# PLC1_3.net
KiCad netlist of a schematic drawn in Altium Designer
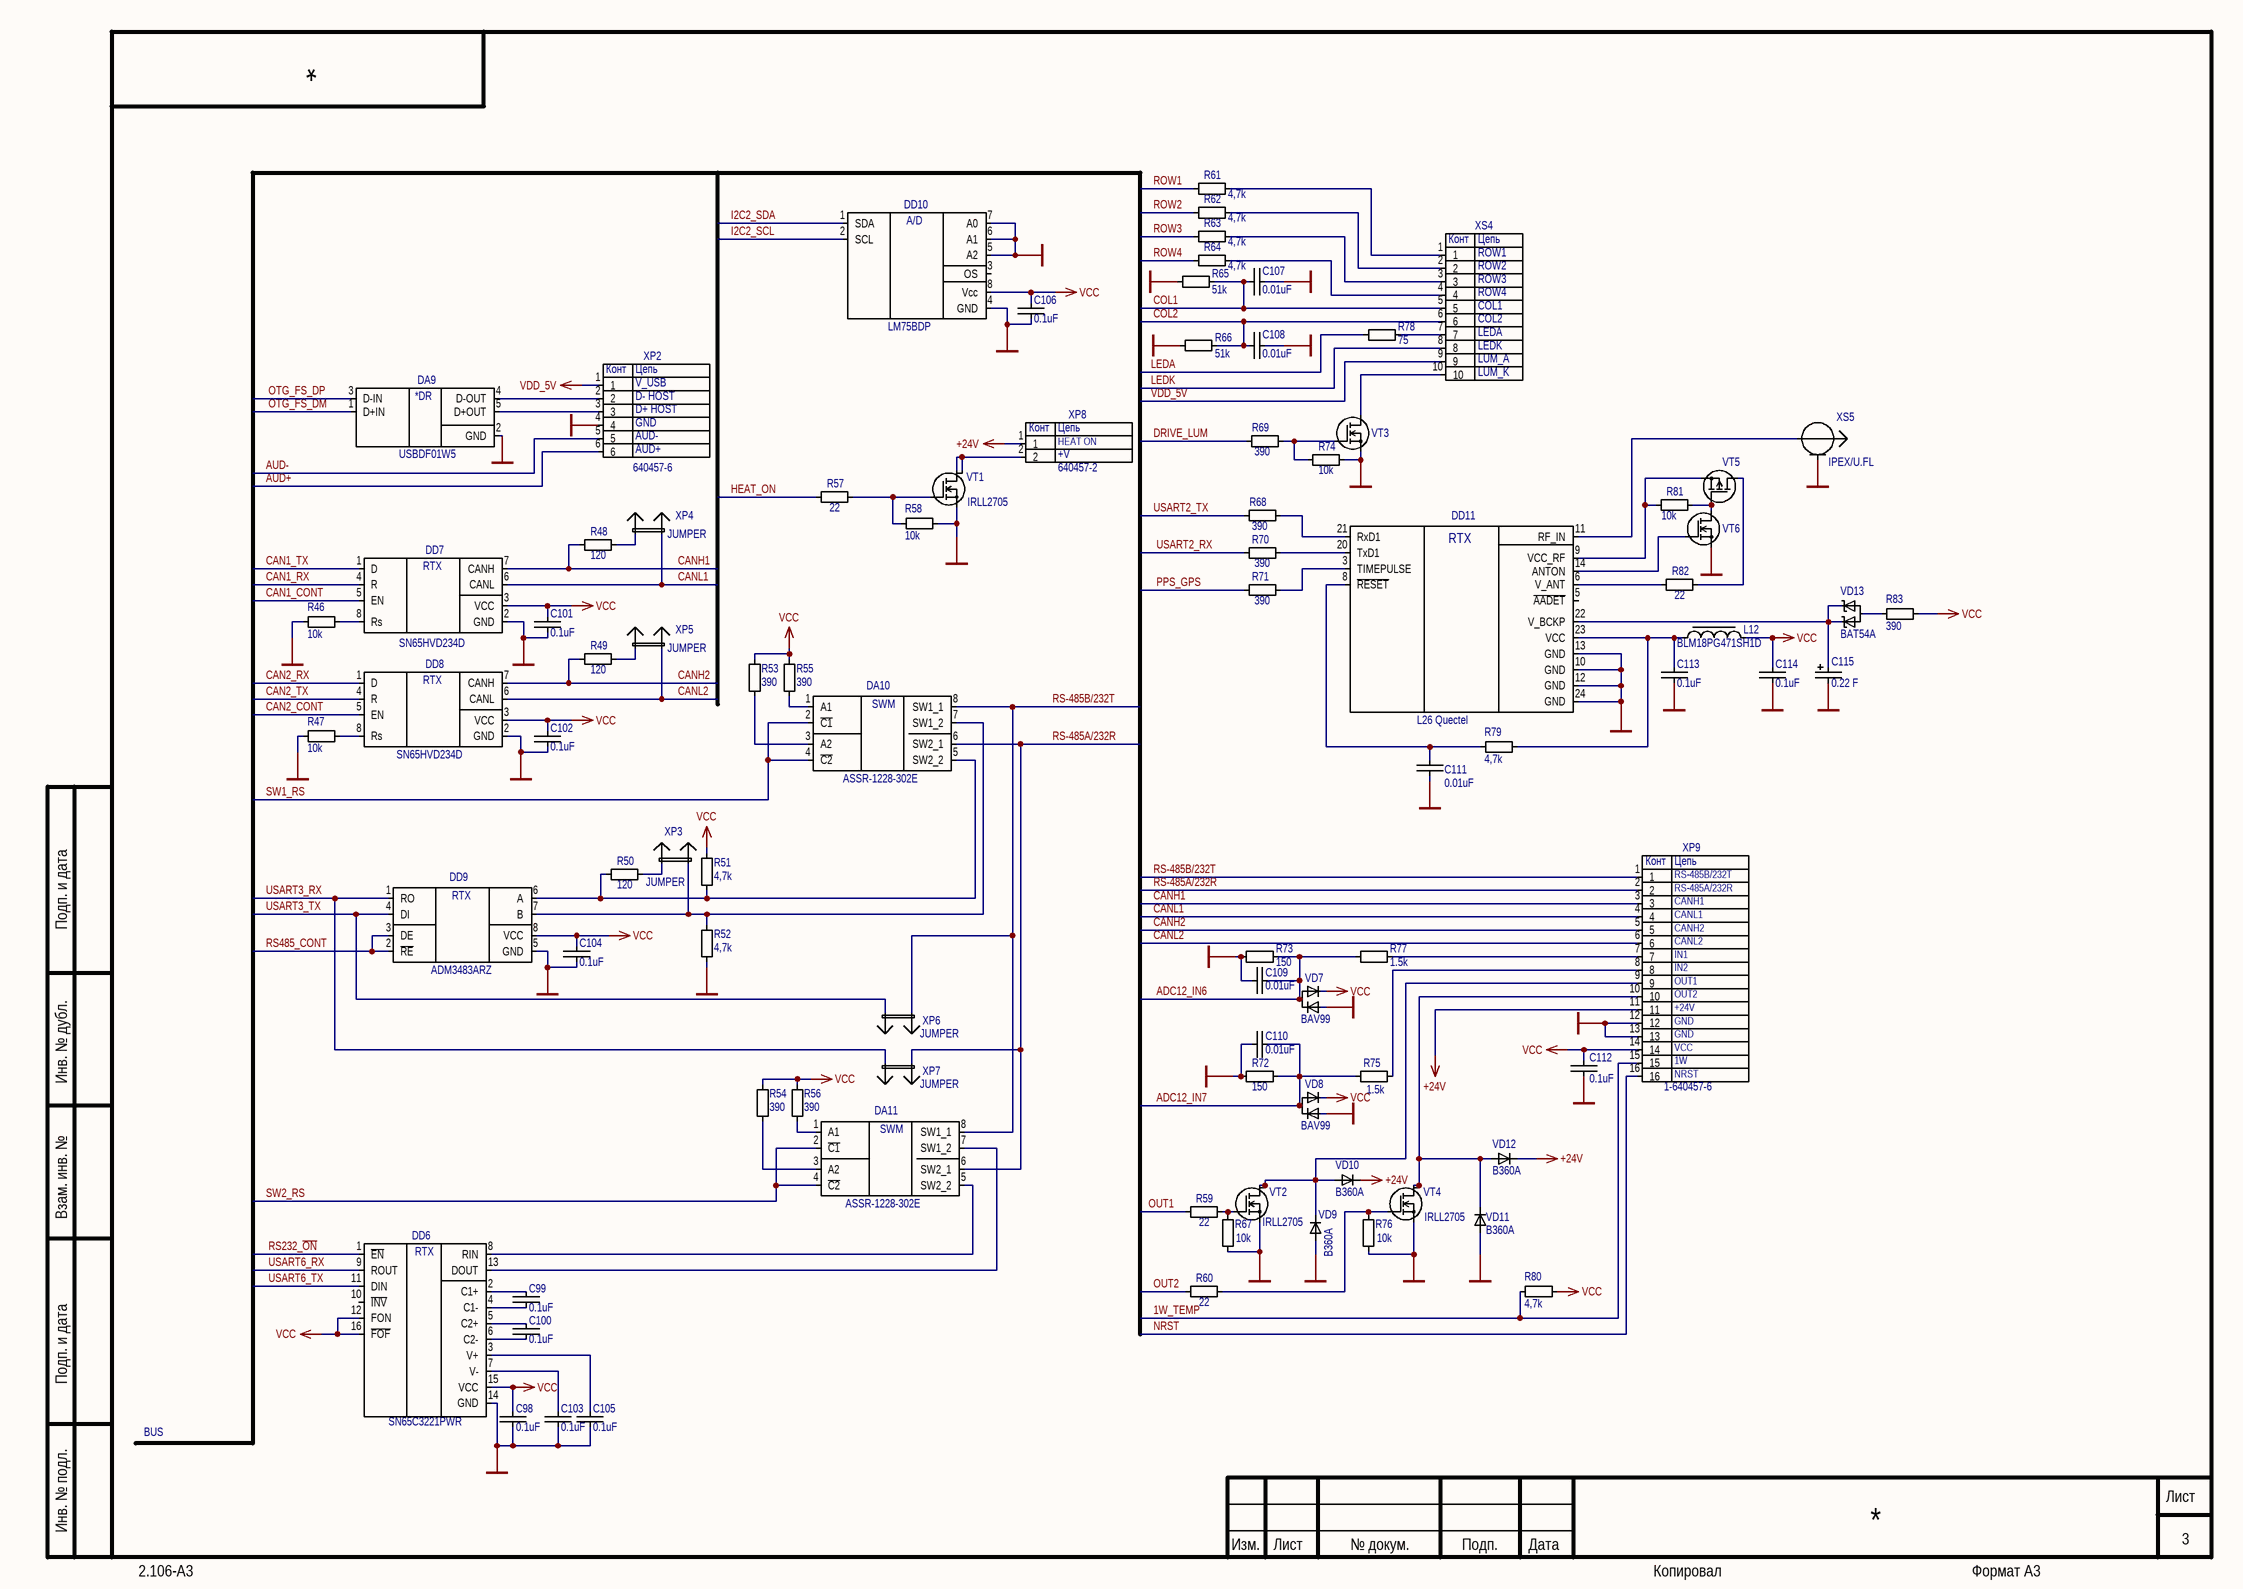
[diagram p0: PLC1_3.SchDoc]

(export (version "E")
  (design (tool "Eeschema 10.0.6"))
  (components
    (comp (ref "C98")
      (value "0.1uF")
      (footprint "CAP_0603")
      (fields (field (name "MANUFACTURER") "AVX") (field (name "PART NUMBER") "0603YC104KAT2A"))
      (libsource (lib "PLC1") (part "Cap_0603"))
    )
    (comp (ref "C99")
      (value "0.1uF")
      (footprint "CAP_0603")
      (fields (field (name "MANUFACTURER") "AVX") (field (name "PART NUMBER") "0603YC104KAT2A"))
      (libsource (lib "PLC1") (part "Cap_0603"))
    )
    (comp (ref "C100")
      (value "0.1uF")
      (footprint "CAP_0603")
      (fields (field (name "MANUFACTURER") "AVX") (field (name "PART NUMBER") "0603YC104KAT2A"))
      (libsource (lib "PLC1") (part "Cap_0603"))
    )
    (comp (ref "C101")
      (value "0.1uF")
      (footprint "CAP_0603")
      (fields (field (name "MANUFACTURER") "AVX") (field (name "PART NUMBER") "0603YC104KAT2A"))
      (libsource (lib "PLC1") (part "Cap_0603"))
    )
    (comp (ref "C102")
      (value "0.1uF")
      (footprint "CAP_0603")
      (fields (field (name "MANUFACTURER") "AVX") (field (name "PART NUMBER") "0603YC104KAT2A"))
      (libsource (lib "PLC1") (part "Cap_0603"))
    )
    (comp (ref "C103")
      (value "0.1uF")
      (footprint "CAP_0603")
      (fields (field (name "MANUFACTURER") "AVX") (field (name "PART NUMBER") "0603YC104KAT2A"))
      (libsource (lib "PLC1") (part "Cap_0603"))
    )
    (comp (ref "C104")
      (value "0.1uF")
      (footprint "CAP_0603")
      (fields (field (name "MANUFACTURER") "AVX") (field (name "PART NUMBER") "0603YC104KAT2A"))
      (libsource (lib "PLC1") (part "Cap_0603"))
    )
    (comp (ref "C105")
      (value "0.1uF")
      (footprint "CAP_0603")
      (fields (field (name "MANUFACTURER") "AVX") (field (name "PART NUMBER") "0603YC104KAT2A"))
      (libsource (lib "PLC1") (part "Cap_0603"))
    )
    (comp (ref "C106")
      (value "0.1uF")
      (footprint "CAP_0603")
      (fields (field (name "MANUFACTURER") "AVX") (field (name "PART NUMBER") "0603YC104KAT2A"))
      (libsource (lib "PLC1") (part "Cap_0603"))
    )
    (comp (ref "C107")
      (value "0.01uF")
      (footprint "CAP_0603")
      (fields (field (name "MANUFACTURER") "AVX") (field (name "PART NUMBER") "0603YC103KAT2A"))
      (libsource (lib "PLC1") (part "Cap_0603"))
    )
    (comp (ref "C108")
      (value "0.01uF")
      (footprint "CAP_0603")
      (fields (field (name "MANUFACTURER") "AVX") (field (name "PART NUMBER") "0603YC103KAT2A"))
      (libsource (lib "PLC1") (part "Cap_0603"))
    )
    (comp (ref "C109")
      (value "0.01uF")
      (footprint "CAP_0603")
      (fields (field (name "MANUFACTURER") "AVX") (field (name "PART NUMBER") "0603YC103KAT2A"))
      (libsource (lib "PLC1") (part "Cap_0603"))
    )
    (comp (ref "C110")
      (value "0.01uF")
      (footprint "CAP_0603")
      (fields (field (name "MANUFACTURER") "AVX") (field (name "PART NUMBER") "0603YC103KAT2A"))
      (libsource (lib "PLC1") (part "Cap_0603"))
    )
    (comp (ref "C111")
      (value "0.01uF")
      (footprint "CAP_0603")
      (fields (field (name "MANUFACTURER") "AVX") (field (name "PART NUMBER") "0603YC103KAT2A"))
      (libsource (lib "PLC1") (part "Cap_0603"))
    )
    (comp (ref "C112")
      (value "0.1uF")
      (footprint "CAP_0603")
      (fields (field (name "MANUFACTURER") "AVX") (field (name "PART NUMBER") "0603YC104KAT2A"))
      (libsource (lib "PLC1") (part "Cap_0603"))
    )
    (comp (ref "C113")
      (value "0.1uF")
      (footprint "CAP_0603")
      (fields (field (name "MANUFACTURER") "AVX") (field (name "PART NUMBER") "0603YC104KAT2A"))
      (libsource (lib "PLC1") (part "Cap_0603"))
    )
    (comp (ref "C114")
      (value "0.1uF")
      (footprint "CAP_0603")
      (fields (field (name "MANUFACTURER") "AVX") (field (name "PART NUMBER") "0603YC104KAT2A"))
      (libsource (lib "PLC1") (part "Cap_0603"))
    )
    (comp (ref "C115")
      (value "0.22 F")
      (footprint "KR-5R5C104-R")
      (description "supercapacitor 0.22 uF")
      (fields (field (name "MANUFACTURER") "Panasonic") (field (name "PART NUMBER") "KR-5R5C224-R"))
      (libsource (lib "PLC1") (part "KR-5R5C104-R"))
    )
    (comp (ref "DA9")
      (value "USBDF01W5")
      (footprint "SOT323-5L")
      (description "Unidirectional 2 lines Filter + ESD")
      (fields (field (name "MANUFACTURER") "ST") (field (name "PART NUMBER") "USBDF01W5"))
      (libsource (lib "PLC1") (part "USBDF01W6"))
    )
    (comp (ref "DA10")
      (value "ASSR-1228-302E")
      (footprint "DIP8_GULL")
      (description "RS-485 PHY")
      (fields (field (name "MANUFACTURER") "AVAGO") (field (name "PART NUMBER") "ASSR-1228-302E"))
      (libsource (lib "PLC1") (part "ASSR-1228-302E"))
    )
    (comp (ref "DA11")
      (value "ASSR-1228-302E")
      (footprint "DIP8_GULL")
      (description "RS-485 PHY")
      (fields (field (name "MANUFACTURER") "AVAGO") (field (name "PART NUMBER") "ASSR-1228-302E"))
      (libsource (lib "PLC1") (part "ASSR-1228-302E"))
    )
    (comp (ref "DD6")
      (value "SN65C3221PWR")
      (footprint "TSSO5x6-G16")
      (description "RS-232 PHY CAN PHY")
      (fields (field (name "MANUFACTURER") "TI") (field (name "PART NUMBER") "SN65C3221PWR"))
      (libsource (lib "PLC1") (part "SN65C3221PWR"))
    )
    (comp (ref "DD7")
      (value "SN65HVD234D")
      (footprint "SOIC8")
      (description "SN65HVD234D CAN PHY")
      (fields (field (name "MANUFACTURER") "TI") (field (name "PART NUMBER") "SN65HVD234D"))
      (libsource (lib "PLC1") (part "SN65HVD234D"))
    )
    (comp (ref "DD8")
      (value "SN65HVD234D")
      (footprint "SOIC8")
      (description "SN65HVD234D CAN PHY")
      (fields (field (name "MANUFACTURER") "TI") (field (name "PART NUMBER") "SN65HVD234D"))
      (libsource (lib "PLC1") (part "SN65HVD234D"))
    )
    (comp (ref "DD9")
      (value "ADM3483")
      (footprint "SOIC8")
      (description "RS-485 PHY")
      (fields (field (name "MANUFACTURER") "Analog Devices") (field (name "PART NUMBER") "ADM3483ARZ"))
      (libsource (lib "PLC1") (part "ADM3483"))
    )
    (comp (ref "DD10")
      (value "LM75BDP")
      (footprint "TSSO3x5-G8/X.4")
      (description "LM75BDP TEMPERATURE SENSOR")
      (fields (field (name "MANUFACTURER") "NXP") (field (name "PART NUMBER") "LM75BDP"))
      (libsource (lib "PLC1") (part "LM75BDP"))
    )
    (comp (ref "DD11")
      (value "L26 Quectel")
      (footprint "VK1612U")
      (description "GPS receiver")
      (fields (field (name "MANUFACTURER") "Quectel") (field (name "PART NUMBER") "L26 Quectel"))
      (libsource (lib "PLC1") (part "L26 Quectel"))
    )
    (comp (ref "L12")
      (value "BLM18PG471SH1D")
      (footprint "R_IND_0603")
      (fields (field (name "MANUFACTURER") "Murata"))
      (libsource (lib "PLC1") (part "FCM1608KF-601T03"))
    )
    (comp (ref "R46")
      (value "10k")
      (footprint "RES_0603")
      (description "0603, 10k")
      (fields (field (name "MANUFACTURER") "Vishay") (field (name "PART NUMBER") "CRCW060310K0JNE"))
      (libsource (lib "PLC1") (part "Res_0603"))
    )
    (comp (ref "R47")
      (value "10k")
      (footprint "RES_0603")
      (description "0603, 10k")
      (fields (field (name "MANUFACTURER") "Vishay") (field (name "PART NUMBER") "CRCW060310K0JNE"))
      (libsource (lib "PLC1") (part "Res_0603"))
    )
    (comp (ref "R48")
      (value "120")
      (footprint "Res_2010")
      (description "2010")
      (fields
        (field (name "MANUFACTURER") "NIC Components Corp.")
        (field (name "PART NUMBER") "NRC50J121TRF")
      )
      (libsource (lib "PLC1") (part "Res_2010"))
    )
    (comp (ref "R49")
      (value "120")
      (footprint "Res_2010")
      (description "2010")
      (fields
        (field (name "MANUFACTURER") "NIC Components Corp.")
        (field (name "PART NUMBER") "NRC50J121TRF")
      )
      (libsource (lib "PLC1") (part "Res_2010"))
    )
    (comp (ref "R50")
      (value "120")
      (footprint "Res_2010")
      (description "2010")
      (fields
        (field (name "MANUFACTURER") "NIC Components Corp.")
        (field (name "PART NUMBER") "NRC50J121TRF")
      )
      (libsource (lib "PLC1") (part "Res_2010"))
    )
    (comp (ref "R51")
      (value "4,7k")
      (footprint "RES_0603")
      (description "0603, 100")
      (fields (field (name "MANUFACTURER") "Vishay") (field (name "PART NUMBER") "CRCW0603-472JRT1"))
      (libsource (lib "PLC1") (part "Res_0603"))
    )
    (comp (ref "R52")
      (value "4,7k")
      (footprint "RES_0603")
      (description "0603, 100")
      (fields (field (name "MANUFACTURER") "Vishay") (field (name "PART NUMBER") "CRCW0603-472JRT1"))
      (libsource (lib "PLC1") (part "Res_0603"))
    )
    (comp (ref "R53")
      (value "390")
      (footprint "RES_0603")
      (description "0603, 390")
      (fields (field (name "MANUFACTURER") "YAGEO") (field (name "PART NUMBER") "RC0603FR-07390RL"))
      (libsource (lib "PLC1") (part "Res_0603"))
    )
    (comp (ref "R54")
      (value "390")
      (footprint "RES_0603")
      (description "0603, 390")
      (fields (field (name "MANUFACTURER") "YAGEO") (field (name "PART NUMBER") "RC0603FR-07390RL"))
      (libsource (lib "PLC1") (part "Res_0603"))
    )
    (comp (ref "R55")
      (value "390")
      (footprint "RES_0603")
      (description "0603, 390")
      (fields (field (name "MANUFACTURER") "YAGEO") (field (name "PART NUMBER") "RC0603FR-07390RL"))
      (libsource (lib "PLC1") (part "Res_0603"))
    )
    (comp (ref "R56")
      (value "390")
      (footprint "RES_0603")
      (description "0603, 390")
      (fields (field (name "MANUFACTURER") "YAGEO") (field (name "PART NUMBER") "RC0603FR-07390RL"))
      (libsource (lib "PLC1") (part "Res_0603"))
    )
    (comp (ref "R57")
      (value "22")
      (footprint "RES_0603")
      (description "0603, 22")
      (fields (field (name "MANUFACTURER") "Vishay") (field (name "PART NUMBER") "CRCW020122R0JNED"))
      (libsource (lib "PLC1") (part "Res_0603"))
    )
    (comp (ref "R58")
      (value "10k")
      (footprint "RES_0603")
      (description "0603, 10k")
      (fields (field (name "MANUFACTURER") "Vishay") (field (name "PART NUMBER") "CRCW060310K0JNE"))
      (libsource (lib "PLC1") (part "Res_0603"))
    )
    (comp (ref "R59")
      (value "22")
      (footprint "RES_0603")
      (description "0603, 22")
      (fields (field (name "MANUFACTURER") "Vishay") (field (name "PART NUMBER") "CRCW020122R0JNED"))
      (libsource (lib "PLC1") (part "Res_0603"))
    )
    (comp (ref "R60")
      (value "22")
      (footprint "RES_0603")
      (description "0603, 22")
      (fields (field (name "MANUFACTURER") "Vishay") (field (name "PART NUMBER") "CRCW020122R0JNED"))
      (libsource (lib "PLC1") (part "Res_0603"))
    )
    (comp (ref "R61")
      (value "4,7k")
      (footprint "Res_0603")
      (description "0603, 100")
      (fields (field (name "MANUFACTURER") "Vishay") (field (name "PART NUMBER") "CRCW0603-472JRT1"))
      (libsource (lib "PLC1") (part "Res_0603"))
    )
    (comp (ref "R62")
      (value "4,7k")
      (footprint "Res_0603")
      (description "0603, 100")
      (fields (field (name "MANUFACTURER") "Vishay") (field (name "PART NUMBER") "CRCW0603-472JRT1"))
      (libsource (lib "PLC1") (part "Res_0603"))
    )
    (comp (ref "R63")
      (value "4,7k")
      (footprint "Res_0603")
      (description "0603, 100")
      (fields (field (name "MANUFACTURER") "Vishay") (field (name "PART NUMBER") "CRCW0603-472JRT1"))
      (libsource (lib "PLC1") (part "Res_0603"))
    )
    (comp (ref "R64")
      (value "4,7k")
      (footprint "Res_0603")
      (description "0603, 100")
      (fields (field (name "MANUFACTURER") "Vishay") (field (name "PART NUMBER") "CRCW0603-472JRT1"))
      (libsource (lib "PLC1") (part "Res_0603"))
    )
    (comp (ref "R65")
      (value "51k")
      (footprint "RES_0603")
      (description "0603, 51k")
      (fields (field (name "MANUFACTURER") "Vishay") (field (name "PART NUMBER") "CRCW0603-513JRT1"))
      (libsource (lib "PLC1") (part "Res_0603"))
    )
    (comp (ref "R66")
      (value "51k")
      (footprint "RES_0603")
      (description "0603, 51k")
      (fields (field (name "MANUFACTURER") "Vishay") (field (name "PART NUMBER") "CRCW0603-513JRT1"))
      (libsource (lib "PLC1") (part "Res_0603"))
    )
    (comp (ref "R67")
      (value "10k")
      (footprint "RES_0603")
      (description "0603, 10k")
      (fields (field (name "MANUFACTURER") "Vishay") (field (name "PART NUMBER") "CRCW060310K0JNE"))
      (libsource (lib "PLC1") (part "Res_0603"))
    )
    (comp (ref "R68")
      (value "390")
      (footprint "RES_0603")
      (description "0603, 390")
      (fields (field (name "MANUFACTURER") "YAGEO") (field (name "PART NUMBER") "RC0603FR-07390RL"))
      (libsource (lib "PLC1") (part "Res_0603"))
    )
    (comp (ref "R69")
      (value "390")
      (footprint "RES_0603")
      (description "0603, 390")
      (fields (field (name "MANUFACTURER") "YAGEO") (field (name "PART NUMBER") "RC0603FR-07390RL"))
      (libsource (lib "PLC1") (part "Res_0603"))
    )
    (comp (ref "R70")
      (value "390")
      (footprint "RES_0603")
      (description "0603, 390")
      (fields (field (name "MANUFACTURER") "YAGEO") (field (name "PART NUMBER") "RC0603FR-07390RL"))
      (libsource (lib "PLC1") (part "Res_0603"))
    )
    (comp (ref "R71")
      (value "390")
      (footprint "RES_0603")
      (description "0603, 390")
      (fields (field (name "MANUFACTURER") "YAGEO") (field (name "PART NUMBER") "RC0603FR-07390RL"))
      (libsource (lib "PLC1") (part "Res_0603"))
    )
    (comp (ref "R72")
      (value "150")
      (footprint "Res_1206")
      (fields
        (field (name "MANUFACTURER") "Vishay")
        (field (name "PART NUMBER") "CRCW1206150RFKEA")
        (field (name "Comment") "Res_1206")
      )
      (libsource (lib "PLC1") (part "Res_1206"))
    )
    (comp (ref "R73")
      (value "150")
      (footprint "Res_1206")
      (fields
        (field (name "MANUFACTURER") "Vishay")
        (field (name "PART NUMBER") "CRCW1206150RFKEA")
        (field (name "Comment") "Res_1206")
      )
      (libsource (lib "PLC1") (part "Res_1206"))
    )
    (comp (ref "R74")
      (value "10k")
      (footprint "RES_0603")
      (description "0603, 10k")
      (fields (field (name "MANUFACTURER") "Vishay") (field (name "PART NUMBER") "CRCW060310K0JNE"))
      (libsource (lib "") (part "Res_0603_1"))
    )
    (comp (ref "R75")
      (value "1.5k")
      (footprint "Res_1206")
      (fields
        (field (name "MANUFACTURER") "Vishay")
        (field (name "PART NUMBER") "CRCW12061K50FKEA")
        (field (name "Comment") "Res_1206")
      )
      (libsource (lib "PLC1") (part "Res_1206"))
    )
    (comp (ref "R76")
      (value "10k")
      (footprint "RES_0603")
      (description "0603, 10k")
      (fields (field (name "MANUFACTURER") "Vishay") (field (name "PART NUMBER") "CRCW060310K0JNE"))
      (libsource (lib "PLC1") (part "Res_0603"))
    )
    (comp (ref "R77")
      (value "1.5k")
      (footprint "Res_1206")
      (fields
        (field (name "MANUFACTURER") "Vishay")
        (field (name "PART NUMBER") "CRCW12061K50FKEA")
        (field (name "Comment") "Res_1206")
      )
      (libsource (lib "PLC1") (part "Res_1206"))
    )
    (comp (ref "R78")
      (value "75")
      (footprint "RES_0603")
      (description "0603")
      (fields (field (name "MANUFACTURER") "YAGEO") (field (name "PART NUMBER") "RC0603JR-0775RL"))
      (libsource (lib "PLC1") (part "Res_0603"))
    )
    (comp (ref "R79")
      (value "4,7k")
      (footprint "Res_0603")
      (description "0603, 100")
      (fields (field (name "MANUFACTURER") "Vishay") (field (name "PART NUMBER") "CRCW0603-472JRT1"))
      (libsource (lib "PLC1") (part "Res_0603"))
    )
    (comp (ref "R80")
      (value "4,7k")
      (footprint "Res_0603")
      (description "0603, 100")
      (fields (field (name "MANUFACTURER") "Vishay") (field (name "PART NUMBER") "CRCW0603-472JRT1"))
      (libsource (lib "PLC1") (part "Res_0603"))
    )
    (comp (ref "R81")
      (value "10k")
      (footprint "RES_0603")
      (description "0603, 10k")
      (fields (field (name "MANUFACTURER") "Vishay") (field (name "PART NUMBER") "CRCW060310K0JNE"))
      (libsource (lib "PLC1") (part "Res_0603"))
    )
    (comp (ref "R82")
      (value "22")
      (footprint "RES_0603")
      (description "0603, 22")
      (fields (field (name "MANUFACTURER") "Vishay") (field (name "PART NUMBER") "CRCW020122R0JNED"))
      (libsource (lib "PLC1") (part "Res_0603"))
    )
    (comp (ref "R83")
      (value "390")
      (footprint "RES_0603")
      (description "0603, 390")
      (fields (field (name "MANUFACTURER") "YAGEO") (field (name "PART NUMBER") "RC0603FR-07390RL"))
      (libsource (lib "PLC1") (part "Res_0603"))
    )
    (comp (ref "VD7")
      (value "BAV99")
      (footprint "SOT-23")
      (fields (field (name "MANUFACTURER") "Fairchild"))
      (libsource (lib "PLC1") (part "BAV99"))
    )
    (comp (ref "VD8")
      (value "BAV99")
      (footprint "SOT-23")
      (fields (field (name "MANUFACTURER") "Fairchild"))
      (libsource (lib "PLC1") (part "BAV99"))
    )
    (comp (ref "VD9")
      (value "B360A")
      (footprint "DO-214AC")
      (fields (field (name "PART NUMBER") "B360A") (field (name "MANUFACTURER") "VISHAY"))
      (libsource (lib "PLC1") (part "S1A"))
    )
    (comp (ref "VD10")
      (value "B360A")
      (footprint "DO-214AC")
      (fields (field (name "PART NUMBER") "B360A") (field (name "MANUFACTURER") "VISHAY"))
      (libsource (lib "") (part "S1A_1"))
    )
    (comp (ref "VD11")
      (value "B360A")
      (footprint "DO-214AC")
      (fields (field (name "PART NUMBER") "B360A") (field (name "MANUFACTURER") "VISHAY"))
      (libsource (lib "PLC1") (part "S1A"))
    )
    (comp (ref "VD12")
      (value "B360A")
      (footprint "DO-214AC")
      (fields (field (name "PART NUMBER") "B360A") (field (name "MANUFACTURER") "VISHAY"))
      (libsource (lib "PLC1") (part "S1A"))
    )
    (comp (ref "VD13") (value "BAT54A") (footprint "SOT-23") (libsource (lib "PLC1") (part "BAT54A")))
    (comp (ref "VT1")
      (value "N-CHAN_SOT-223")
      (footprint "SOT-223")
      (fields (field (name "PART NUMBER") "IRLL2705"))
      (libsource (lib "PLC1") (part "N-CHAN_SOT-223"))
    )
    (comp (ref "VT2")
      (value "N-CHAN_SOT-223")
      (footprint "SOT-223")
      (fields (field (name "PART NUMBER") "IRLL2705"))
      (libsource (lib "PLC1") (part "N-CHAN_SOT-223"))
    )
    (comp (ref "VT3")
      (value "N-CHAN_SOT-23")
      (footprint "SOT-23")
      (fields (field (name "MANUFACTURER") "IR") (field (name "PART NUMBER") "IRLML2502"))
      (libsource (lib "") (part "N-CHAN_SOT-23_1"))
    )
    (comp (ref "VT4")
      (value "N-CHAN_SOT-223")
      (footprint "SOT-223")
      (fields (field (name "PART NUMBER") "IRLL2705"))
      (libsource (lib "PLC1") (part "N-CHAN_SOT-223"))
    )
    (comp (ref "VT5")
      (value "IRLML6402")
      (footprint "SOT-23")
      (libsource (lib "PLC1") (part "P-CHAN_SOT-23"))
    )
    (comp (ref "VT6")
      (value "N-CHAN_SOT-23")
      (footprint "SOT-23")
      (fields (field (name "MANUFACTURER") "IR") (field (name "PART NUMBER") "IRLML2502"))
      (libsource (lib "PLC1") (part "N-CHAN_SOT-23"))
    )
    (comp (ref "XP2")
      (value "640457-6")
      (footprint "640457-6")
      (fields (field (name "MANUFACTURER") "TE"))
      (libsource (lib "PLC1") (part "640457-6"))
    )
    (comp (ref "XP3")
      (value "JUMPER")
      (footprint "PLS2-R")
      (description "JUMPER 2.54")
      (fields (field (name "MANUFACTURER") "TE") (field (name "PART NUMBER") "PLS-2R"))
      (libsource (lib "PLC1") (part "PLS-2 R"))
    )
    (comp (ref "XP4")
      (value "JUMPER")
      (footprint "PLS2-R")
      (description "JUMPER 2.54")
      (fields (field (name "MANUFACTURER") "TE") (field (name "PART NUMBER") "PLS-2R"))
      (libsource (lib "PLC1") (part "PLS-2 R"))
    )
    (comp (ref "XP5")
      (value "JUMPER")
      (footprint "PLS2-R")
      (description "JUMPER 2.54")
      (fields (field (name "MANUFACTURER") "TE") (field (name "PART NUMBER") "PLS-2R"))
      (libsource (lib "PLC1") (part "PLS-2 R"))
    )
    (comp (ref "XP6")
      (value "JUMPER")
      (footprint "JMPTOPOLOGY")
      (description "JUMPER 2.54")
      (fields (field (name "MANUFACTURER") "TE"))
      (libsource (lib "PLC1") (part "TOPOLOGYJMP"))
    )
    (comp (ref "XP7")
      (value "JUMPER")
      (footprint "JMPTOPOLOGY")
      (description "JUMPER 2.54")
      (fields (field (name "MANUFACTURER") "TE"))
      (libsource (lib "PLC1") (part "TOPOLOGYJMP"))
    )
    (comp (ref "XP8")
      (value "640457-2")
      (footprint "640457-2")
      (fields (field (name "MANUFACTURER") "TE"))
      (libsource (lib "PLC1") (part "640457-2"))
    )
    (comp (ref "XP9")
      (value "1-640457-6")
      (footprint "1-640457-6")
      (fields (field (name "MANUFACTURER") "TE"))
      (libsource (lib "PLC1") (part "1-640457-6"))
    )
    (comp (ref "XS4")
      (value "522711079")
      (footprint "522711079")
      (fields (field (name "MANUFACTURER") "Molex"))
      (libsource (lib "PLC1") (part "522711079"))
    )
    (comp (ref "XS5")
      (value "IPEX/U.FL")
      (footprint "IPEX MHFI")
      (description "IPEX/U.FL male pcb SMT")
      (fields
        (field (name "MANUFACTURER") "taoglas limited")
        (field (name "PACKAGEREFERENCE") "IPEX/U.FL")
        (field (name "PART NUMBER") "20279-001E-01")
      )
      (libsource (lib "PLC1") (part "IPEX/U.FL"))
    )
  )
  (nets
    (net (code "1") (name "+24V") (class "Default")
      (node (ref "VD10") (pin "2") (pinfunction "2_2") (pintype "passive"))
      (node (ref "VD12") (pin "2") (pinfunction "2_2") (pintype "passive"))
      (node (ref "XP8") (pin "1") (pinfunction "1_1") (pintype "passive"))
      (node (ref "XP9") (pin "11") (pinfunction "11_11") (pintype "passive"))
    )
    (net (code "2") (name "/1W_TEMP") (class "Default")
      (node (ref "R80") (pin "2") (pinfunction "2_2") (pintype "passive"))
      (node (ref "XP9") (pin "15") (pinfunction "15_15") (pintype "passive"))
    )
    (net (code "3") (name "/ADC12_IN6") (class "Default")
      (node (ref "C109") (pin "2") (pinfunction "2_2") (pintype "passive"))
      (node (ref "R73") (pin "1") (pinfunction "1_1") (pintype "passive"))
      (node (ref "R77") (pin "2") (pinfunction "2_2") (pintype "passive"))
      (node (ref "VD7") (pin "3") (pinfunction "3_3") (pintype "passive"))
    )
    (net (code "4") (name "/ADC12_IN7") (class "Default")
      (node (ref "C110") (pin "2") (pinfunction "2_2") (pintype "passive"))
      (node (ref "R72") (pin "1") (pinfunction "1_1") (pintype "passive"))
      (node (ref "R75") (pin "2") (pinfunction "2_2") (pintype "passive"))
      (node (ref "VD8") (pin "3") (pinfunction "3_3") (pintype "passive"))
    )
    (net (code "5") (name "/AUD+") (class "Default")
      (node (ref "XP2") (pin "6") (pinfunction "6_6") (pintype "passive"))
    )
    (net (code "6") (name "/AUD-") (class "Default")
      (node (ref "XP2") (pin "5") (pinfunction "5_5") (pintype "passive"))
    )
    (net (code "7") (name "/CAN1_CONT") (class "Default")
      (node (ref "DD7") (pin "5") (pinfunction "EN_5") (pintype "passive"))
    )
    (net (code "8") (name "/CAN1_RX") (class "Default")
      (node (ref "DD7") (pin "4") (pinfunction "R_4") (pintype "passive"))
    )
    (net (code "9") (name "/CAN1_TX") (class "Default")
      (node (ref "DD7") (pin "1") (pinfunction "D_1") (pintype "passive"))
    )
    (net (code "10") (name "/CAN2_CONT") (class "Default")
      (node (ref "DD8") (pin "5") (pinfunction "EN_5") (pintype "passive"))
    )
    (net (code "11") (name "/CAN2_RX") (class "Default")
      (node (ref "DD8") (pin "1") (pinfunction "D_1") (pintype "passive"))
    )
    (net (code "12") (name "/CAN2_TX") (class "Default")
      (node (ref "DD8") (pin "4") (pinfunction "R_4") (pintype "passive"))
    )
    (net (code "13") (name "/CANH1") (class "Default")
      (node (ref "DD7") (pin "7") (pinfunction "CANH_7") (pintype "passive"))
      (node (ref "R48") (pin "1") (pinfunction "1_1") (pintype "passive"))
      (node (ref "XP9") (pin "3") (pinfunction "3_3") (pintype "passive"))
    )
    (net (code "14") (name "/CANH2") (class "Default")
      (node (ref "DD8") (pin "7") (pinfunction "CANH_7") (pintype "passive"))
      (node (ref "R49") (pin "1") (pinfunction "1_1") (pintype "passive"))
      (node (ref "XP9") (pin "5") (pinfunction "5_5") (pintype "passive"))
    )
    (net (code "15") (name "/CANL1") (class "Default")
      (node (ref "DD7") (pin "6") (pinfunction "CANL_6") (pintype "passive"))
      (node (ref "XP4") (pin "2") (pinfunction "2_2") (pintype "passive"))
      (node (ref "XP9") (pin "4") (pinfunction "4_4") (pintype "passive"))
    )
    (net (code "16") (name "/CANL2") (class "Default")
      (node (ref "DD8") (pin "6") (pinfunction "CANL_6") (pintype "passive"))
      (node (ref "XP5") (pin "2") (pinfunction "2_2") (pintype "passive"))
      (node (ref "XP9") (pin "6") (pinfunction "6_6") (pintype "passive"))
    )
    (net (code "17") (name "/COL1") (class "Default")
      (node (ref "C107") (pin "2") (pinfunction "2_2") (pintype "passive"))
      (node (ref "R65") (pin "1") (pinfunction "1_1") (pintype "passive"))
      (node (ref "XS4") (pin "5") (pinfunction "5_5") (pintype "passive"))
    )
    (net (code "18") (name "/COL2") (class "Default")
      (node (ref "C108") (pin "2") (pinfunction "2_2") (pintype "passive"))
      (node (ref "R66") (pin "1") (pinfunction "1_1") (pintype "passive"))
      (node (ref "XS4") (pin "6") (pinfunction "6_6") (pintype "passive"))
    )
    (net (code "19") (name "/DRIVE_LUM") (class "Default")
      (node (ref "R69") (pin "1") (pinfunction "1_1") (pintype "passive"))
    )
    (net (code "20") (name "/HEAT_ON") (class "Default")
      (node (ref "R57") (pin "1") (pinfunction "1_1") (pintype "passive"))
    )
    (net (code "21") (name "/I2C2_SCL") (class "Default")
      (node (ref "DD10") (pin "2") (pinfunction "SCL_2") (pintype "passive"))
    )
    (net (code "22") (name "/I2C2_SDA") (class "Default")
      (node (ref "DD10") (pin "1") (pinfunction "SDA_1") (pintype "passive"))
    )
    (net (code "23") (name "/LEDA") (class "Default")
      (node (ref "R78") (pin "2") (pinfunction "2_2") (pintype "passive"))
    )
    (net (code "24") (name "/LEDK") (class "Default")
      (node (ref "XS4") (pin "8") (pinfunction "8_8") (pintype "passive"))
    )
    (net (code "25") (name "/NRST") (class "Default")
      (node (ref "XP9") (pin "16") (pinfunction "16_16") (pintype "passive"))
    )
    (net (code "26") (name "/OTG_FS_DM") (class "Default")
      (node (ref "DA9") (pin "1") (pinfunction "D+IN_1") (pintype "passive"))
    )
    (net (code "27") (name "/OTG_FS_DP") (class "Default")
      (node (ref "DA9") (pin "3") (pinfunction "D-IN_3") (pintype "passive"))
    )
    (net (code "28") (name "/OUT1") (class "Default")
      (node (ref "R59") (pin "1") (pinfunction "1_1") (pintype "passive"))
    )
    (net (code "29") (name "/OUT2") (class "Default")
      (node (ref "R60") (pin "1") (pinfunction "1_1") (pintype "passive"))
    )
    (net (code "30") (name "/PPS_GPS") (class "Default")
      (node (ref "R71") (pin "1") (pinfunction "1_1") (pintype "passive"))
    )
    (net (code "31") (name "/ROW1") (class "Default")
      (node (ref "R61") (pin "2") (pinfunction "2_2") (pintype "passive"))
    )
    (net (code "32") (name "/ROW2") (class "Default")
      (node (ref "R62") (pin "2") (pinfunction "2_2") (pintype "passive"))
    )
    (net (code "33") (name "/ROW3") (class "Default")
      (node (ref "R63") (pin "2") (pinfunction "2_2") (pintype "passive"))
    )
    (net (code "34") (name "/ROW4") (class "Default")
      (node (ref "R64") (pin "2") (pinfunction "2_2") (pintype "passive"))
    )
    (net (code "35") (name "/RS-485A{slash}232R") (class "Default")
      (node (ref "DA10") (pin "6") (pinfunction "SW2_1_6") (pintype "passive"))
      (node (ref "DA11") (pin "6") (pinfunction "SW2_1_6") (pintype "passive"))
      (node (ref "XP7") (pin "1") (pinfunction "1_1") (pintype "passive"))
      (node (ref "XP9") (pin "2") (pinfunction "2_2") (pintype "passive"))
    )
    (net (code "36") (name "/RS-485B{slash}232T") (class "Default")
      (node (ref "DA10") (pin "8") (pinfunction "SW1_1_8") (pintype "passive"))
      (node (ref "DA11") (pin "8") (pinfunction "SW1_1_8") (pintype "passive"))
      (node (ref "XP6") (pin "1") (pinfunction "1_1") (pintype "passive"))
      (node (ref "XP9") (pin "1") (pinfunction "1_1") (pintype "passive"))
    )
    (net (code "37") (name "/RS232_~{ON}") (class "Default")
      (node (ref "DD6") (pin "1") (pinfunction "~{EN}_1") (pintype "passive"))
    )
    (net (code "38") (name "/RS485_CONT") (class "Default")
      (node (ref "DD9") (pin "2") (pinfunction "~{RE}_2") (pintype "passive"))
      (node (ref "DD9") (pin "3") (pinfunction "DE_3") (pintype "passive"))
    )
    (net (code "39") (name "/SW1_RS") (class "Default")
      (node (ref "DA10") (pin "2") (pinfunction "~{C1}_2") (pintype "passive"))
      (node (ref "DA10") (pin "4") (pinfunction "~{C2}_4") (pintype "passive"))
    )
    (net (code "40") (name "/SW2_RS") (class "Default")
      (node (ref "DA11") (pin "2") (pinfunction "~{C1}_2") (pintype "passive"))
      (node (ref "DA11") (pin "4") (pinfunction "~{C2}_4") (pintype "passive"))
    )
    (net (code "41") (name "/USART2_RX") (class "Default")
      (node (ref "R70") (pin "1") (pinfunction "1_1") (pintype "passive"))
    )
    (net (code "42") (name "/USART2_TX") (class "Default")
      (node (ref "R68") (pin "1") (pinfunction "1_1") (pintype "passive"))
    )
    (net (code "43") (name "/USART3_RX") (class "Default")
      (node (ref "DD9") (pin "1") (pinfunction "RO_1") (pintype "passive"))
      (node (ref "XP7") (pin "2") (pinfunction "2_2") (pintype "passive"))
    )
    (net (code "44") (name "/USART3_TX") (class "Default")
      (node (ref "DD9") (pin "4") (pinfunction "DI_4") (pintype "passive"))
      (node (ref "XP6") (pin "2") (pinfunction "2_2") (pintype "passive"))
    )
    (net (code "45") (name "/USART6_RX") (class "Default")
      (node (ref "DD6") (pin "9") (pinfunction "ROUT_9") (pintype "passive"))
    )
    (net (code "46") (name "/USART6_TX") (class "Default")
      (node (ref "DD6") (pin "11") (pinfunction "DIN_11") (pintype "passive"))
    )
    (net (code "47") (name "GND") (class "Default")
      (node (ref "C101") (pin "2") (pinfunction "2_2") (pintype "passive"))
      (node (ref "C102") (pin "2") (pinfunction "2_2") (pintype "passive"))
      (node (ref "C103") (pin "2") (pinfunction "2_2") (pintype "passive"))
      (node (ref "C104") (pin "2") (pinfunction "2_2") (pintype "passive"))
      (node (ref "C105") (pin "2") (pinfunction "2_2") (pintype "passive"))
      (node (ref "C106") (pin "2") (pinfunction "2_2") (pintype "passive"))
      (node (ref "C107") (pin "1") (pinfunction "1_1") (pintype "passive"))
      (node (ref "C108") (pin "1") (pinfunction "1_1") (pintype "passive"))
      (node (ref "C109") (pin "1") (pinfunction "1_1") (pintype "passive"))
      (node (ref "C110") (pin "1") (pinfunction "1_1") (pintype "passive"))
      (node (ref "C111") (pin "2") (pinfunction "2_2") (pintype "passive"))
      (node (ref "C112") (pin "2") (pinfunction "2_2") (pintype "passive"))
      (node (ref "C113") (pin "2") (pinfunction "2_2") (pintype "passive"))
      (node (ref "C114") (pin "2") (pinfunction "2_2") (pintype "passive"))
      (node (ref "C115") (pin "2") (pinfunction "2_2") (pintype "passive"))
      (node (ref "C98") (pin "2") (pinfunction "2_2") (pintype "passive"))
      (node (ref "DA9") (pin "2") (pinfunction "GND_2") (pintype "passive"))
      (node (ref "DD10") (pin "4") (pinfunction "GND_4") (pintype "passive"))
      (node (ref "DD10") (pin "5") (pinfunction "A2_5") (pintype "passive"))
      (node (ref "DD10") (pin "6") (pinfunction "A1_6") (pintype "passive"))
      (node (ref "DD10") (pin "7") (pinfunction "A0_7") (pintype "passive"))
      (node (ref "DD11") (pin "10") (pinfunction "GND_10") (pintype "passive"))
      (node (ref "DD11") (pin "12") (pinfunction "GND_12") (pintype "passive"))
      (node (ref "DD11") (pin "13") (pinfunction "GND_13") (pintype "passive"))
      (node (ref "DD11") (pin "24") (pinfunction "GND_24") (pintype "passive"))
      (node (ref "DD6") (pin "14") (pinfunction "GND_14") (pintype "passive"))
      (node (ref "DD7") (pin "2") (pinfunction "GND_2") (pintype "passive"))
      (node (ref "DD8") (pin "2") (pinfunction "GND_2") (pintype "passive"))
      (node (ref "DD9") (pin "5") (pinfunction "GND_5") (pintype "passive"))
      (node (ref "R46") (pin "2") (pinfunction "2_2") (pintype "passive"))
      (node (ref "R47") (pin "2") (pinfunction "2_2") (pintype "passive"))
      (node (ref "R52") (pin "2") (pinfunction "2_2") (pintype "passive"))
      (node (ref "R58") (pin "1") (pinfunction "1_1") (pintype "passive"))
      (node (ref "R65") (pin "2") (pinfunction "2_2") (pintype "passive"))
      (node (ref "R66") (pin "2") (pinfunction "2_2") (pintype "passive"))
      (node (ref "R67") (pin "1") (pinfunction "1_1") (pintype "passive"))
      (node (ref "R72") (pin "2") (pinfunction "2_2") (pintype "passive"))
      (node (ref "R73") (pin "2") (pinfunction "2_2") (pintype "passive"))
      (node (ref "R74") (pin "1") (pinfunction "1_1") (pintype "passive"))
      (node (ref "R76") (pin "1") (pinfunction "1_1") (pintype "passive"))
      (node (ref "VD11") (pin "1") (pinfunction "1_1") (pintype "passive"))
      (node (ref "VD7") (pin "1") (pinfunction "1_1") (pintype "passive"))
      (node (ref "VD8") (pin "1") (pinfunction "1_1") (pintype "passive"))
      (node (ref "VD9") (pin "1") (pinfunction "1_1") (pintype "passive"))
      (node (ref "VT1") (pin "3") (pinfunction "3_3") (pintype "passive"))
      (node (ref "VT2") (pin "3") (pinfunction "3_3") (pintype "passive"))
      (node (ref "VT3") (pin "2") (pinfunction "2_2") (pintype "passive"))
      (node (ref "VT4") (pin "3") (pinfunction "3_3") (pintype "passive"))
      (node (ref "VT6") (pin "2") (pinfunction "2_2") (pintype "passive"))
      (node (ref "XP2") (pin "4") (pinfunction "4_4") (pintype "passive"))
      (node (ref "XP9") (pin "12") (pinfunction "12_12") (pintype "passive"))
      (node (ref "XP9") (pin "13") (pinfunction "13_13") (pintype "passive"))
      (node (ref "XS5") (pin "2") (pinfunction "2_2") (pintype "passive"))
    )
    (net (code "48") (name "Net-(DA9-D+OUT)") (class "Default")
      (node (ref "DA9") (pin "5") (pinfunction "D+OUT_5") (pintype "passive"))
      (node (ref "XP2") (pin "3") (pinfunction "3_3") (pintype "passive"))
    )
    (net (code "49") (name "Net-(DA9-D-OUT)") (class "Default")
      (node (ref "DA9") (pin "4") (pinfunction "D-OUT_4") (pintype "passive"))
      (node (ref "XP2") (pin "2") (pinfunction "2_2") (pintype "passive"))
    )
    (net (code "50") (name "Net-(DA10-A1)") (class "Default")
      (node (ref "DA10") (pin "1") (pinfunction "A1_1") (pintype "passive"))
      (node (ref "R55") (pin "2") (pinfunction "2_2") (pintype "passive"))
    )
    (net (code "51") (name "Net-(DA10-A2)") (class "Default")
      (node (ref "DA10") (pin "3") (pinfunction "A2_3") (pintype "passive"))
      (node (ref "R53") (pin "2") (pinfunction "2_2") (pintype "passive"))
    )
    (net (code "52") (name "Net-(DA10-SW1_2)") (class "Default")
      (node (ref "DA10") (pin "7") (pinfunction "SW1_2_7") (pintype "passive"))
      (node (ref "DD9") (pin "7") (pinfunction "B_7") (pintype "passive"))
      (node (ref "R52") (pin "1") (pinfunction "1_1") (pintype "passive"))
      (node (ref "XP3") (pin "2") (pinfunction "2_2") (pintype "passive"))
    )
    (net (code "53") (name "Net-(DA10-SW2_2)") (class "Default")
      (node (ref "DA10") (pin "5") (pinfunction "SW2_2_5") (pintype "passive"))
      (node (ref "DD9") (pin "6") (pinfunction "A_6") (pintype "passive"))
      (node (ref "R50") (pin "1") (pinfunction "1_1") (pintype "passive"))
      (node (ref "R51") (pin "2") (pinfunction "2_2") (pintype "passive"))
    )
    (net (code "54") (name "Net-(DA11-A1)") (class "Default")
      (node (ref "DA11") (pin "1") (pinfunction "A1_1") (pintype "passive"))
      (node (ref "R56") (pin "2") (pinfunction "2_2") (pintype "passive"))
    )
    (net (code "55") (name "Net-(DA11-A2)") (class "Default")
      (node (ref "DA11") (pin "3") (pinfunction "A2_3") (pintype "passive"))
      (node (ref "R54") (pin "2") (pinfunction "2_2") (pintype "passive"))
    )
    (net (code "56") (name "Net-(DA11-SW1_2)") (class "Default")
      (node (ref "DA11") (pin "7") (pinfunction "SW1_2_7") (pintype "passive"))
      (node (ref "DD6") (pin "13") (pinfunction "DOUT_13") (pintype "passive"))
    )
    (net (code "57") (name "Net-(DA11-SW2_2)") (class "Default")
      (node (ref "DA11") (pin "5") (pinfunction "SW2_2_5") (pintype "passive"))
      (node (ref "DD6") (pin "8") (pinfunction "RIN_8") (pintype "passive"))
    )
    (net (code "58") (name "Net-(DD6-C1+)") (class "Default")
      (node (ref "C99") (pin "1") (pinfunction "1_1") (pintype "passive"))
      (node (ref "DD6") (pin "2") (pinfunction "C1+_2") (pintype "passive"))
    )
    (net (code "59") (name "Net-(DD6-C1-)") (class "Default")
      (node (ref "C99") (pin "2") (pinfunction "2_2") (pintype "passive"))
      (node (ref "DD6") (pin "4") (pinfunction "C1-_4") (pintype "passive"))
    )
    (net (code "60") (name "Net-(DD6-C2+)") (class "Default")
      (node (ref "C100") (pin "1") (pinfunction "1_1") (pintype "passive"))
      (node (ref "DD6") (pin "5") (pinfunction "C2+_5") (pintype "passive"))
    )
    (net (code "61") (name "Net-(DD6-C2-)") (class "Default")
      (node (ref "C100") (pin "2") (pinfunction "2_2") (pintype "passive"))
      (node (ref "DD6") (pin "6") (pinfunction "C2-_6") (pintype "passive"))
    )
    (net (code "62") (name "Net-(DD6-V+)") (class "Default")
      (node (ref "C105") (pin "1") (pinfunction "1_1") (pintype "passive"))
      (node (ref "DD6") (pin "3") (pinfunction "V+_3") (pintype "passive"))
    )
    (net (code "63") (name "Net-(DD6-V-)") (class "Default")
      (node (ref "C103") (pin "1") (pinfunction "1_1") (pintype "passive"))
      (node (ref "DD6") (pin "7") (pinfunction "V-_7") (pintype "passive"))
    )
    (net (code "64") (name "Net-(DD7-Rs)") (class "Default")
      (node (ref "DD7") (pin "8") (pinfunction "Rs_8") (pintype "passive"))
      (node (ref "R46") (pin "1") (pinfunction "1_1") (pintype "passive"))
    )
    (net (code "65") (name "Net-(DD8-Rs)") (class "Default")
      (node (ref "DD8") (pin "8") (pinfunction "Rs_8") (pintype "passive"))
      (node (ref "R47") (pin "1") (pinfunction "1_1") (pintype "passive"))
    )
    (net (code "66") (name "Net-(DD11-ANTON)") (class "Default")
      (node (ref "DD11") (pin "14") (pinfunction "ANTON_14") (pintype "passive"))
      (node (ref "VT6") (pin "1") (pinfunction "1_1") (pintype "passive"))
    )
    (net (code "67") (name "Net-(DD11-RF_IN)") (class "Default")
      (node (ref "DD11") (pin "11") (pinfunction "RF_IN_11") (pintype "passive"))
      (node (ref "XS5") (pin "1") (pinfunction "1_1") (pintype "passive"))
    )
    (net (code "68") (name "Net-(DD11-RxD1)") (class "Default")
      (node (ref "DD11") (pin "21") (pinfunction "RxD1_21") (pintype "passive"))
      (node (ref "R68") (pin "2") (pinfunction "2_2") (pintype "passive"))
    )
    (net (code "69") (name "Net-(DD11-TIMEPULSE)") (class "Default")
      (node (ref "DD11") (pin "3") (pinfunction "TIMEPULSE_3") (pintype "passive"))
      (node (ref "R71") (pin "2") (pinfunction "2_2") (pintype "passive"))
    )
    (net (code "70") (name "Net-(DD11-TxD1)") (class "Default")
      (node (ref "DD11") (pin "20") (pinfunction "TxD1_20") (pintype "passive"))
      (node (ref "R70") (pin "2") (pinfunction "2_2") (pintype "passive"))
    )
    (net (code "71") (name "Net-(DD11-VCC)") (class "Default")
      (node (ref "C113") (pin "1") (pinfunction "1_1") (pintype "passive"))
      (node (ref "DD11") (pin "23") (pinfunction "VCC_23") (pintype "passive"))
      (node (ref "L12") (pin "2") (pinfunction "2_2") (pintype "passive"))
      (node (ref "R79") (pin "1") (pinfunction "1_1") (pintype "passive"))
    )
    (net (code "72") (name "Net-(DD11-VCC_RF)") (class "Default")
      (node (ref "DD11") (pin "9") (pinfunction "VCC_RF_9") (pintype "passive"))
      (node (ref "R81") (pin "2") (pinfunction "2_2") (pintype "passive"))
      (node (ref "VT5") (pin "2") (pinfunction "2_2") (pintype "passive"))
    )
    (net (code "73") (name "Net-(DD11-V_ANT)") (class "Default")
      (node (ref "DD11") (pin "6") (pinfunction "V_ANT_6") (pintype "passive"))
      (node (ref "R82") (pin "1") (pinfunction "1_1") (pintype "passive"))
    )
    (net (code "74") (name "Net-(DD11-V_BCKP)") (class "Default")
      (node (ref "C115") (pin "1") (pinfunction "1_1") (pintype "passive"))
      (node (ref "DD11") (pin "22") (pinfunction "V_BCKP_22") (pintype "passive"))
      (node (ref "VD13") (pin "1") (pinfunction "1_1") (pintype "passive"))
      (node (ref "VD13") (pin "2") (pinfunction "2_2") (pintype "passive"))
    )
    (net (code "75") (name "Net-(DD11-~{RESET})") (class "Default")
      (node (ref "C111") (pin "1") (pinfunction "1_1") (pintype "passive"))
      (node (ref "DD11") (pin "8") (pinfunction "~{RESET}_8") (pintype "passive"))
      (node (ref "R79") (pin "2") (pinfunction "2_2") (pintype "passive"))
    )
    (net (code "76") (name "Net-(R48-Pad2)") (class "Default")
      (node (ref "R48") (pin "2") (pinfunction "2_2") (pintype "passive"))
      (node (ref "XP4") (pin "1") (pinfunction "1_1") (pintype "passive"))
    )
    (net (code "77") (name "Net-(R49-Pad2)") (class "Default")
      (node (ref "R49") (pin "2") (pinfunction "2_2") (pintype "passive"))
      (node (ref "XP5") (pin "1") (pinfunction "1_1") (pintype "passive"))
    )
    (net (code "78") (name "Net-(R50-Pad2)") (class "Default")
      (node (ref "R50") (pin "2") (pinfunction "2_2") (pintype "passive"))
      (node (ref "XP3") (pin "1") (pinfunction "1_1") (pintype "passive"))
    )
    (net (code "79") (name "Net-(R57-Pad2)") (class "Default")
      (node (ref "R57") (pin "2") (pinfunction "2_2") (pintype "passive"))
      (node (ref "R58") (pin "2") (pinfunction "2_2") (pintype "passive"))
      (node (ref "VT1") (pin "1") (pinfunction "1_1") (pintype "passive"))
    )
    (net (code "80") (name "Net-(R59-Pad2)") (class "Default")
      (node (ref "R59") (pin "2") (pinfunction "2_2") (pintype "passive"))
      (node (ref "R67") (pin "2") (pinfunction "2_2") (pintype "passive"))
      (node (ref "VT2") (pin "1") (pinfunction "1_1") (pintype "passive"))
    )
    (net (code "81") (name "Net-(R60-Pad2)") (class "Default")
      (node (ref "R60") (pin "2") (pinfunction "2_2") (pintype "passive"))
      (node (ref "R76") (pin "2") (pinfunction "2_2") (pintype "passive"))
      (node (ref "VT4") (pin "1") (pinfunction "1_1") (pintype "passive"))
    )
    (net (code "82") (name "Net-(R61-Pad1)") (class "Default")
      (node (ref "R61") (pin "1") (pinfunction "1_1") (pintype "passive"))
      (node (ref "XS4") (pin "1") (pinfunction "1_1") (pintype "passive"))
    )
    (net (code "83") (name "Net-(R62-Pad1)") (class "Default")
      (node (ref "R62") (pin "1") (pinfunction "1_1") (pintype "passive"))
      (node (ref "XS4") (pin "2") (pinfunction "2_2") (pintype "passive"))
    )
    (net (code "84") (name "Net-(R63-Pad1)") (class "Default")
      (node (ref "R63") (pin "1") (pinfunction "1_1") (pintype "passive"))
      (node (ref "XS4") (pin "3") (pinfunction "3_3") (pintype "passive"))
    )
    (net (code "85") (name "Net-(R64-Pad1)") (class "Default")
      (node (ref "R64") (pin "1") (pinfunction "1_1") (pintype "passive"))
      (node (ref "XS4") (pin "4") (pinfunction "4_4") (pintype "passive"))
    )
    (net (code "86") (name "Net-(R69-Pad2)") (class "Default")
      (node (ref "R69") (pin "2") (pinfunction "2_2") (pintype "passive"))
      (node (ref "R74") (pin "2") (pinfunction "2_2") (pintype "passive"))
      (node (ref "VT3") (pin "1") (pinfunction "1_1") (pintype "passive"))
    )
    (net (code "87") (name "Net-(R75-Pad1)") (class "Default")
      (node (ref "R75") (pin "1") (pinfunction "1_1") (pintype "passive"))
      (node (ref "XP9") (pin "8") (pinfunction "8_8") (pintype "passive"))
    )
    (net (code "88") (name "Net-(R77-Pad1)") (class "Default")
      (node (ref "R77") (pin "1") (pinfunction "1_1") (pintype "passive"))
      (node (ref "XP9") (pin "7") (pinfunction "7_7") (pintype "passive"))
    )
    (net (code "89") (name "Net-(R78-Pad1)") (class "Default")
      (node (ref "R78") (pin "1") (pinfunction "1_1") (pintype "passive"))
      (node (ref "XS4") (pin "7") (pinfunction "7_7") (pintype "passive"))
    )
    (net (code "90") (name "Net-(R81-Pad1)") (class "Default")
      (node (ref "R81") (pin "1") (pinfunction "1_1") (pintype "passive"))
      (node (ref "VT5") (pin "1") (pinfunction "1_1") (pintype "passive"))
      (node (ref "VT6") (pin "3") (pinfunction "3_3") (pintype "passive"))
    )
    (net (code "91") (name "Net-(R82-Pad2)") (class "Default")
      (node (ref "R82") (pin "2") (pinfunction "2_2") (pintype "passive"))
      (node (ref "VT5") (pin "3") (pinfunction "3_3") (pintype "passive"))
    )
    (net (code "92") (name "Net-(R83-Pad1)") (class "Default")
      (node (ref "R83") (pin "1") (pinfunction "1_1") (pintype "passive"))
      (node (ref "VD13") (pin "3") (pinfunction "3_3") (pintype "passive"))
    )
    (net (code "93") (name "Net-(VD10-Pad1)") (class "Default")
      (node (ref "VD10") (pin "1") (pinfunction "1_1") (pintype "passive"))
      (node (ref "VD9") (pin "2") (pinfunction "2_2") (pintype "passive"))
      (node (ref "VT2") (pin "2") (pinfunction "2_2") (pintype "passive"))
      (node (ref "VT2") (pin "4") (pinfunction "4_4") (pintype "passive"))
      (node (ref "XP9") (pin "9") (pinfunction "9_9") (pintype "passive"))
    )
    (net (code "94") (name "Net-(VD11-Pad2)") (class "Default")
      (node (ref "VD11") (pin "2") (pinfunction "2_2") (pintype "passive"))
      (node (ref "VD12") (pin "1") (pinfunction "1_1") (pintype "passive"))
      (node (ref "VT4") (pin "2") (pinfunction "2_2") (pintype "passive"))
      (node (ref "VT4") (pin "4") (pinfunction "4_4") (pintype "passive"))
      (node (ref "XP9") (pin "10") (pinfunction "10_10") (pintype "passive"))
    )
    (net (code "95") (name "Net-(VT1-Pad2)") (class "Default")
      (node (ref "VT1") (pin "2") (pinfunction "2_2") (pintype "passive"))
      (node (ref "VT1") (pin "4") (pinfunction "4_4") (pintype "passive"))
      (node (ref "XP8") (pin "2") (pinfunction "2_2") (pintype "passive"))
    )
    (net (code "96") (name "Net-(VT3-Pad3)") (class "Default")
      (node (ref "VT3") (pin "3") (pinfunction "3_3") (pintype "passive"))
      (node (ref "XS4") (pin "10") (pinfunction "10_10") (pintype "passive"))
    )
    (net (code "97") (name "VCC") (class "Default")
      (node (ref "C101") (pin "1") (pinfunction "1_1") (pintype "passive"))
      (node (ref "C102") (pin "1") (pinfunction "1_1") (pintype "passive"))
      (node (ref "C104") (pin "1") (pinfunction "1_1") (pintype "passive"))
      (node (ref "C106") (pin "1") (pinfunction "1_1") (pintype "passive"))
      (node (ref "C112") (pin "1") (pinfunction "1_1") (pintype "passive"))
      (node (ref "C114") (pin "1") (pinfunction "1_1") (pintype "passive"))
      (node (ref "C98") (pin "1") (pinfunction "1_1") (pintype "passive"))
      (node (ref "DD10") (pin "8") (pinfunction "Vcc_8") (pintype "passive"))
      (node (ref "DD6") (pin "12") (pinfunction "FON_12") (pintype "passive"))
      (node (ref "DD6") (pin "15") (pinfunction "VCC_15") (pintype "passive"))
      (node (ref "DD6") (pin "16") (pinfunction "~{FOF}_16") (pintype "passive"))
      (node (ref "DD7") (pin "3") (pinfunction "VCC_3") (pintype "passive"))
      (node (ref "DD8") (pin "3") (pinfunction "VCC_3") (pintype "passive"))
      (node (ref "DD9") (pin "8") (pinfunction "VCC_8") (pintype "passive"))
      (node (ref "L12") (pin "1") (pinfunction "1_1") (pintype "passive"))
      (node (ref "R51") (pin "1") (pinfunction "1_1") (pintype "passive"))
      (node (ref "R53") (pin "1") (pinfunction "1_1") (pintype "passive"))
      (node (ref "R54") (pin "1") (pinfunction "1_1") (pintype "passive"))
      (node (ref "R55") (pin "1") (pinfunction "1_1") (pintype "passive"))
      (node (ref "R56") (pin "1") (pinfunction "1_1") (pintype "passive"))
      (node (ref "R80") (pin "1") (pinfunction "1_1") (pintype "passive"))
      (node (ref "R83") (pin "2") (pinfunction "2_2") (pintype "passive"))
      (node (ref "VD7") (pin "2") (pinfunction "2_2") (pintype "passive"))
      (node (ref "VD8") (pin "2") (pinfunction "2_2") (pintype "passive"))
      (node (ref "XP9") (pin "14") (pinfunction "14_14") (pintype "passive"))
    )
    (net (code "98") (name "VDD_5V") (class "Default")
      (node (ref "XP2") (pin "1") (pinfunction "1_1") (pintype "passive"))
      (node (ref "XS4") (pin "9") (pinfunction "9_9") (pintype "passive"))
    )
    (net (code "99") (name "unconnected-(DD6-~{INV}-Pad10)") (class "Default")
      (node (ref "DD6") (pin "10") (pinfunction "~{INV}_10") (pintype "passive"))
    )
    (net (code "100") (name "unconnected-(DD10-OS-Pad3)") (class "Default")
      (node (ref "DD10") (pin "3") (pinfunction "OS_3") (pintype "passive"))
    )
    (net (code "101") (name "unconnected-(DD11-~{AADET}-Pad5)") (class "Default")
      (node (ref "DD11") (pin "5") (pinfunction "~{AADET}_5") (pintype "passive"))
    )
  )
)
